# MCU.net
KiCad netlist of a schematic drawn in Altium Designer
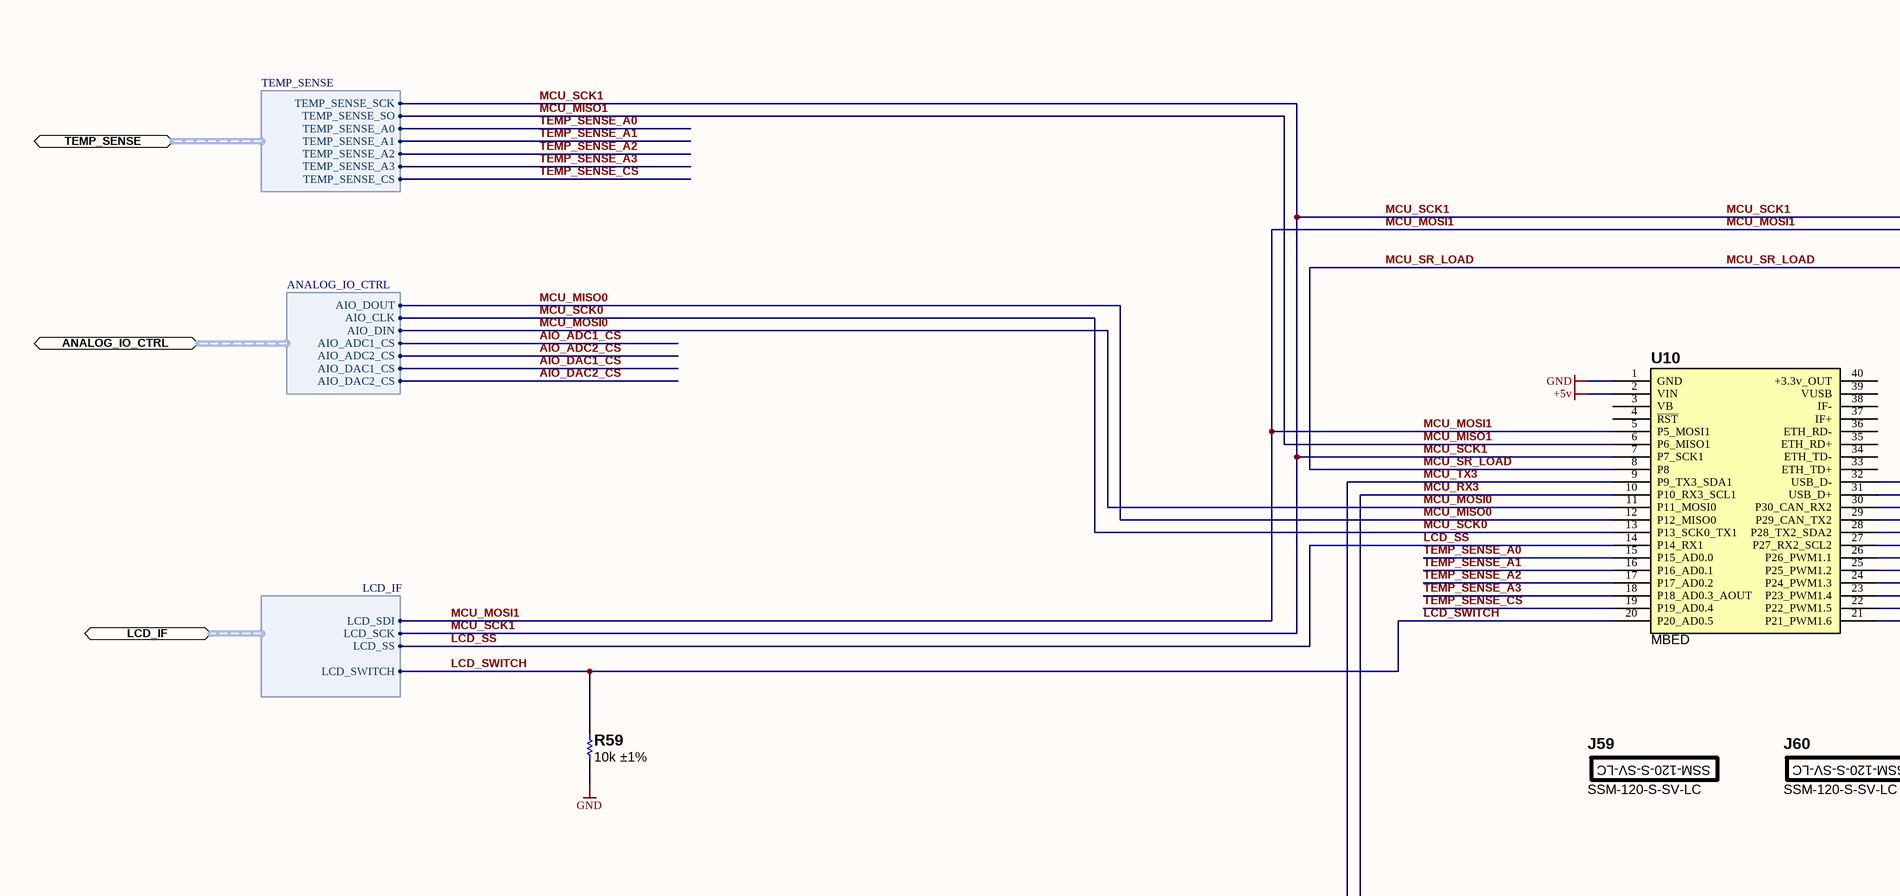
[diagram p0: MCU.SchDoc, top left]
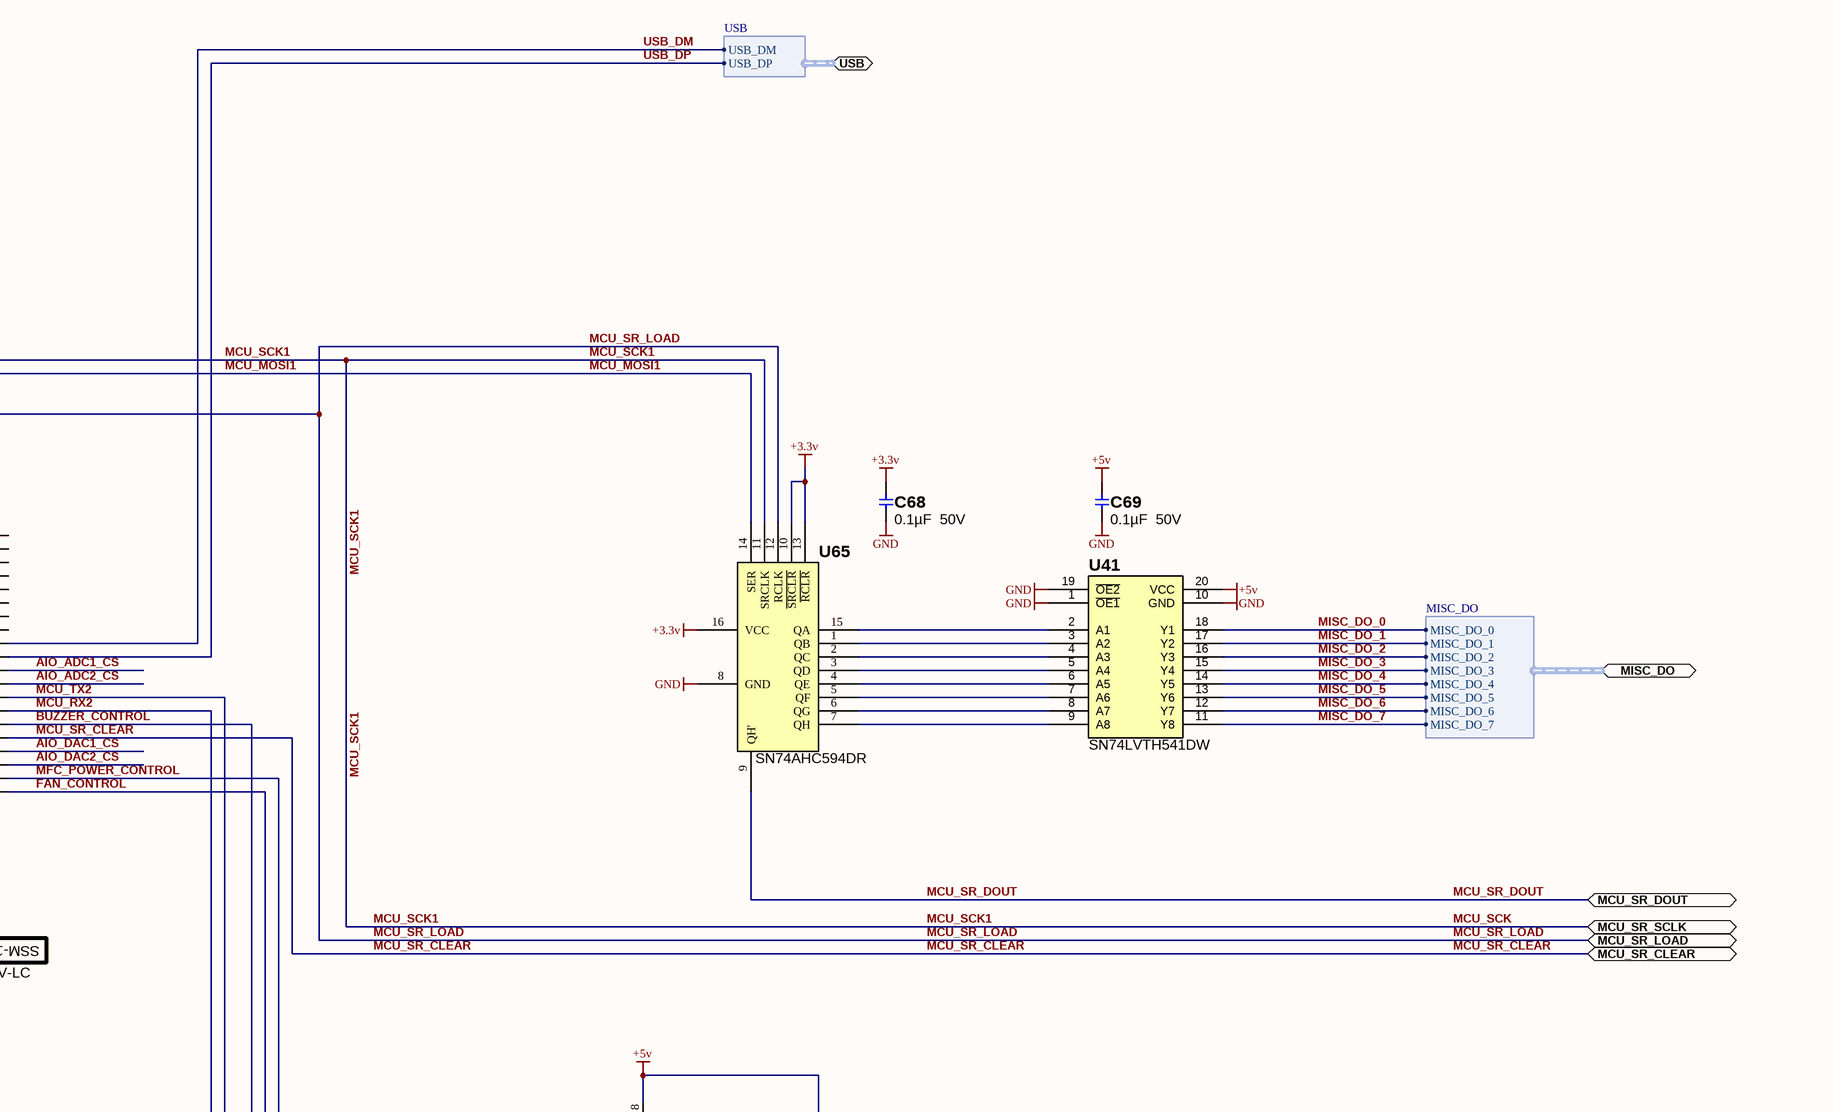
[diagram p1: MCU.SchDoc, top right]
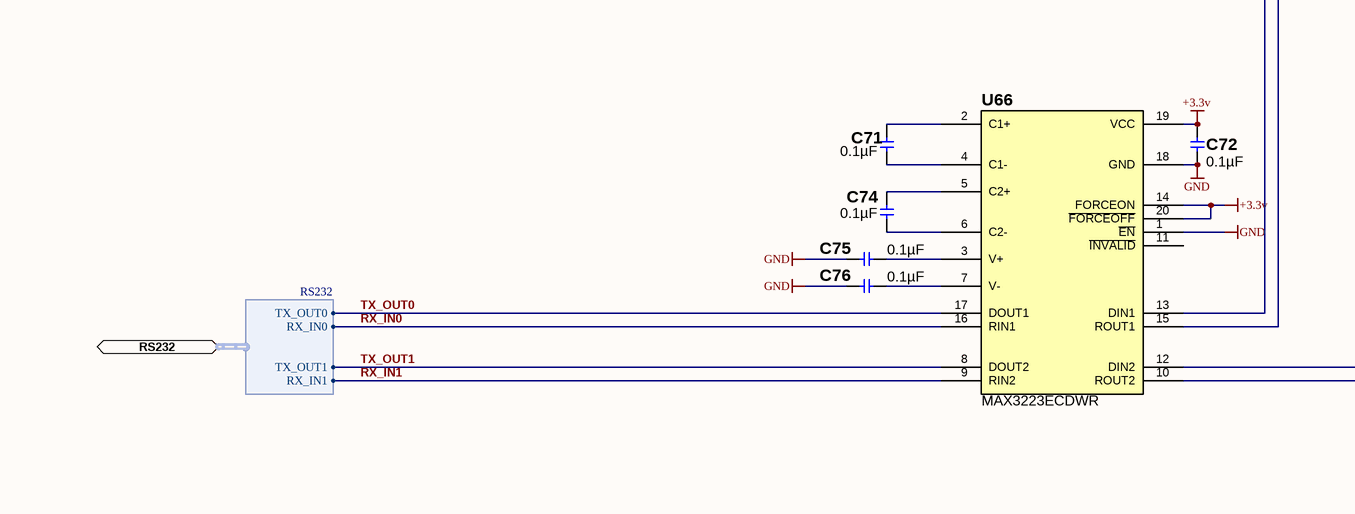
[diagram p2: MCU.SchDoc, bottom left]
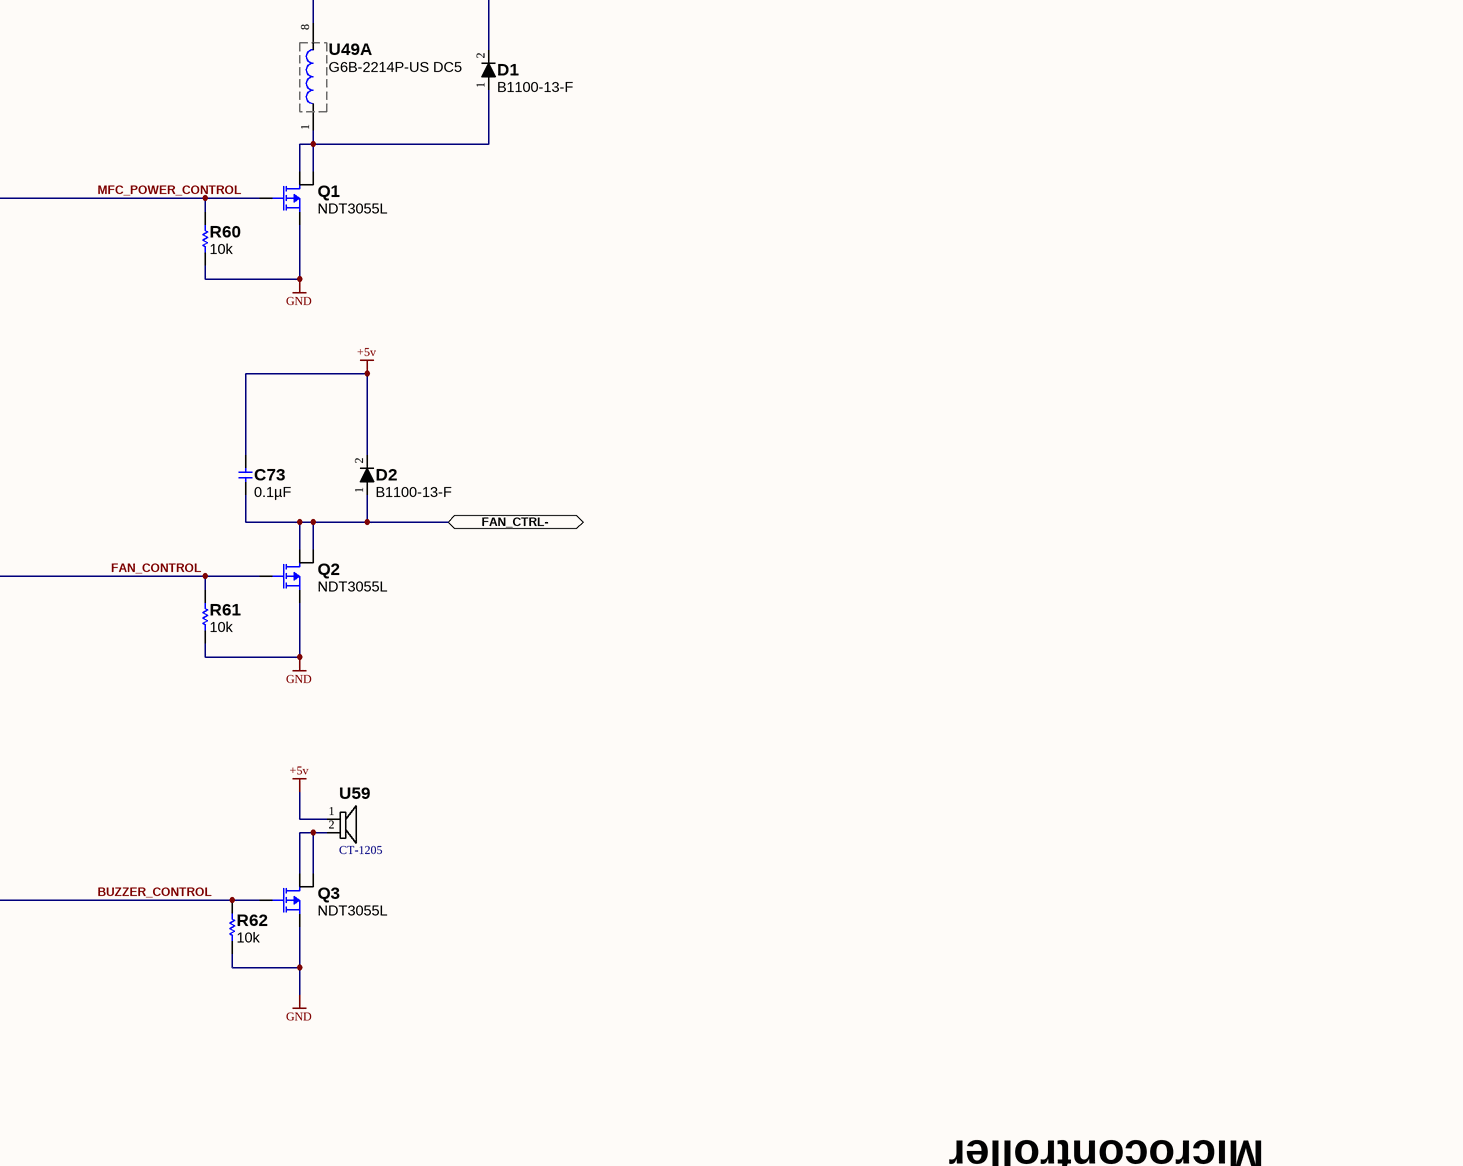
[diagram p3: MCU.SchDoc, bottom right]

(export (version "E")
  (design (tool "Eeschema 10.0.6"))
  (components
    (comp (ref "C68")
      (value "0.1µF  50V")
      (footprint "C0805_LD")
      (description "CAP CER 0.1UF 50V 10% X7R 0805")
      (fields
        (field (name "MANUFACTURER PART NUMBER") "GRM21BR71H104KA01L")
        (field (name "MANUFACTURER") "Murata Electronics North America")
      )
      (libsource (lib "Capacitors") (part "C_2P_NP"))
    )
    (comp (ref "C69")
      (value "0.1µF  50V")
      (footprint "C0805_LD")
      (description "CAP CER 0.1UF 50V 10% X7R 0805")
      (fields
        (field (name "MANUFACTURER PART NUMBER") "GRM21BR71H104KA01L")
        (field (name "MANUFACTURER") "Murata Electronics North America")
      )
      (libsource (lib "Capacitors") (part "C_2P_NP"))
    )
    (comp (ref "C71")
      (value "0.1µF")
      (footprint "C0805_LD")
      (description "CAP CER 0.1UF 50V 10% X7R 0805")
      (fields
        (field (name "MANUFACTURER PART NUMBER") "GRM21BR71H104KA01L")
        (field (name "MANUFACTURER") "Murata Electronics North America")
      )
      (libsource (lib "Capacitors") (part "C_2P_NP"))
    )
    (comp (ref "C72")
      (value "0.1µF")
      (footprint "C0805_LD")
      (description "CAP CER 0.1UF 50V 10% X7R 0805")
      (fields
        (field (name "MANUFACTURER PART NUMBER") "GRM21BR71H104KA01L")
        (field (name "MANUFACTURER") "Murata Electronics North America")
      )
      (libsource (lib "Capacitors") (part "C_2P_NP"))
    )
    (comp (ref "C73")
      (value "0.1µF")
      (footprint "C0805_LD")
      (description "CAP CER 0.1UF 50V 10% X7R 0805")
      (fields
        (field (name "MANUFACTURER PART NUMBER") "GRM21BR71H104KA01L")
        (field (name "MANUFACTURER") "Murata Electronics North America")
      )
      (libsource (lib "Capacitors") (part "C_2P_NP"))
    )
    (comp (ref "C74")
      (value "0.1µF")
      (footprint "C0805_LD")
      (description "CAP CER 0.1UF 50V 10% X7R 0805")
      (fields
        (field (name "MANUFACTURER PART NUMBER") "GRM21BR71H104KA01L")
        (field (name "MANUFACTURER") "Murata Electronics North America")
      )
      (libsource (lib "Capacitors") (part "C_2P_NP"))
    )
    (comp (ref "C75")
      (value "0.1µF")
      (footprint "C0805_LD")
      (description "CAP CER 0.1UF 50V 10% X7R 0805")
      (fields
        (field (name "MANUFACTURER PART NUMBER") "GRM21BR71H104KA01L")
        (field (name "MANUFACTURER") "Murata Electronics North America")
      )
      (libsource (lib "Capacitors") (part "C_2P_NP"))
    )
    (comp (ref "C76")
      (value "0.1µF")
      (footprint "C0805_LD")
      (description "CAP CER 0.1UF 50V 10% X7R 0805")
      (fields
        (field (name "MANUFACTURER PART NUMBER") "GRM21BR71H104KA01L")
        (field (name "MANUFACTURER") "Murata Electronics North America")
      )
      (libsource (lib "Capacitors") (part "C_2P_NP"))
    )
    (comp (ref "D1")
      (value "B1100-13-F")
      (footprint "D_SMA_P")
      (description "DIODE SCHOTTKY 100V 1A SMA")
      (fields (field (name "MANUFACTURER") "Diodes Inc"))
      (libsource (lib "Diodes") (part "DP_1A_2C"))
    )
    (comp (ref "D2")
      (value "B1100-13-F")
      (footprint "D_SMA_P")
      (description "DIODE SCHOTTKY 100V 1A SMA")
      (fields (field (name "MANUFACTURER") "Diodes Inc"))
      (libsource (lib "Diodes") (part "DP_1A_2C"))
    )
    (comp (ref "J59")
      (value "SSM-120-S-SV-LC")
      (description "SAMTEC - SSM-120-S-SV-LC - .025 SOCKET STRIPS")
      (fields (field (name "MANUFACTURER") "SAMTEC"))
      (libsource (lib "151214_2") (part "SSM-120-S-SV-LC (BOM ITEM)"))
    )
    (comp (ref "J60")
      (value "SSM-120-S-SV-LC")
      (description "SAMTEC - SSM-120-S-SV-LC - .025 SOCKET STRIPS")
      (fields (field (name "MANUFACTURER") "SAMTEC"))
      (libsource (lib "151214_2") (part "SSM-120-S-SV-LC (BOM ITEM)"))
    )
    (comp (ref "Q1")
      (value "NDT3055L")
      (footprint "SOT223")
      (description "MOSFET N-CH 60V 4A SOT-223-4")
      (fields (field (name "MANUFACTURER") "Fairchild Semiconductor"))
      (libsource (lib "eTransistor") (part "NDT3055L"))
    )
    (comp (ref "Q2")
      (value "NDT3055L")
      (footprint "SOT223")
      (description "MOSFET N-CH 60V 4A SOT-223-4")
      (fields (field (name "MANUFACTURER") "Fairchild Semiconductor"))
      (libsource (lib "eTransistor") (part "NDT3055L"))
    )
    (comp (ref "Q3")
      (value "NDT3055L")
      (footprint "SOT223")
      (description "MOSFET N-CH 60V 4A SOT-223-4")
      (fields (field (name "MANUFACTURER") "Fairchild Semiconductor"))
      (libsource (lib "eTransistor") (part "NDT3055L"))
    )
    (comp (ref "R59")
      (value "10k ±1%")
      (footprint "R0805_LD")
      (description "RES 10K OHM 1/8W 1% 0805 SMD")
      (fields
        (field (name "MANUFACTURER PART NUMBER") "ERJ-6ENF1002V")
        (field (name "MANUFACTURER") "Panasonic Electronic Components")
      )
      (libsource (lib "Resistors") (part "R_2P"))
    )
    (comp (ref "R60")
      (value "10k")
      (footprint "R0805_LD")
      (description "RES 10K OHM 1/8W 1% 0805 SMD")
      (fields
        (field (name "MANUFACTURER PART NUMBER") "ERJ-6ENF1002V")
        (field (name "MANUFACTURER") "Panasonic Electronic Components")
      )
      (libsource (lib "Resistors") (part "R_2P"))
    )
    (comp (ref "R61")
      (value "10k")
      (footprint "R0805_LD")
      (description "RES 10K OHM 1/8W 1% 0805 SMD")
      (fields
        (field (name "MANUFACTURER PART NUMBER") "ERJ-6ENF1002V")
        (field (name "MANUFACTURER") "Panasonic Electronic Components")
      )
      (libsource (lib "Resistors") (part "R_2P"))
    )
    (comp (ref "R62")
      (value "10k")
      (footprint "R0805_LD")
      (description "RES 10K OHM 1/8W 1% 0805 SMD")
      (fields
        (field (name "MANUFACTURER PART NUMBER") "ERJ-6ENF1002V")
        (field (name "MANUFACTURER") "Panasonic Electronic Components")
      )
      (libsource (lib "Resistors") (part "R_2P"))
    )
    (comp (ref "U10")
      (value "MBED")
      (footprint "MBED_SURFACEMOUNT_SOCKET")
      (description "DEVELOPMENT BOARD LPC1768 MBED")
      (fields
        (field (name "MANUFACTURER") "NXP Semiconductors")
        (field (name "MANUFACTURER PART NUMBER") "OM11043")
      )
      (libsource (lib "eModule") (part "OM11043"))
    )
    (comp (ref "U41")
      (value "SN74LVTH541DW")
      (footprint "SOIC127P1030X265-20L")
      (description "IC BUFF/DVR TRI-ST 8BIT 20SOIC")
      (fields (field (name "MANUFACTURER") "Texas Instruments"))
      (libsource (lib "eIC") (part "SN74LVTH541DW"))
    )
    (comp (ref "U49")
      (value "G6B-2214P-US DC5")
      (footprint "G6B-2214P-US")
      (description "RELAY GENERAL PURPOSE DPST 5A 5V")
      (fields (field (name "MANUFACTURER") "Omron Electronics Inc-EMC Div"))
      (libsource (lib "eElectroMechanical") (part "G6B-2214P-US DC5"))
    )
    (comp (ref "U59")
      (value "CT-1205")
      (footprint "CT-1205")
      (fields (field (name "MANUFACTURER") "CUI Inc") (field (name "SOURCE") "Digikey"))
      (libsource (lib "eAudio") (part "CT-1205"))
    )
    (comp (ref "U65")
      (value "SN74AHC594DR")
      (footprint "SOIC127P600X145-16L")
      (description "IC SHIFT REGISTER 8BIT 16-SOIC")
      (fields (field (name "MANUFACTURER") "Texas Instruments"))
      (libsource (lib "eIC") (part "SN74AHC594DR"))
    )
    (comp (ref "U66")
      (value "MAX3223ECDWR")
      (footprint "SOIC127P1030X265-20L")
      (description "IC RS232 3V5.5V DRVR ESD 20-SOIC")
      (fields (field (name "MANUFACTURER") "Texas Instruments"))
      (libsource (lib "eIC") (part "MAX3223ECDWR"))
    )
  )
  (nets
    (net (code "7") (name "+3.3v") (class "Default")
      (node (ref "C68") (pin "2") (pinfunction "2_2") (pintype "passive"))
      (node (ref "C72") (pin "2") (pinfunction "2_2") (pintype "passive"))
      (node (ref "U65") (pin "10") (pinfunction "~{SRCLR}_10") (pintype "passive"))
      (node (ref "U65") (pin "13") (pinfunction "~{RCLR}_13") (pintype "passive"))
      (node (ref "U65") (pin "16") (pinfunction "VCC_16") (pintype "passive"))
      (node (ref "U66") (pin "14") (pinfunction "FORCEON_14") (pintype "passive"))
      (node (ref "U66") (pin "19") (pinfunction "VCC_19") (pintype "passive"))
      (node (ref "U66") (pin "20") (pinfunction "~{FORCEOFF}_20") (pintype "passive"))
    )
    (net (code "8") (name "+5v") (class "Default")
      (node (ref "C69") (pin "2") (pinfunction "2_2") (pintype "passive"))
      (node (ref "C73") (pin "2") (pinfunction "2_2") (pintype "passive"))
      (node (ref "D1") (pin "2") (pinfunction "K_2") (pintype "passive"))
      (node (ref "D2") (pin "2") (pinfunction "K_2") (pintype "passive"))
      (node (ref "U10") (pin "2") (pinfunction "VIN_2") (pintype "passive"))
      (node (ref "U41") (pin "20") (pinfunction "VCC_20") (pintype "passive"))
      (node (ref "U49") (pin "8") (pinfunction "8_8") (pintype "passive"))
      (node (ref "U59") (pin "1") (pinfunction "+_1") (pintype "passive"))
    )
    (net (code "9") (name "/AIO_ADC1_CS") (class "Default")
      (node (ref "U10") (pin "30") (pinfunction "P30_CAN_RX2_30") (pintype "passive"))
    )
    (net (code "10") (name "/AIO_ADC2_CS") (class "Default")
      (node (ref "U10") (pin "29") (pinfunction "P29_CAN_TX2_29") (pintype "passive"))
    )
    (net (code "11") (name "/AIO_DAC1_CS") (class "Default")
      (node (ref "U10") (pin "24") (pinfunction "P24_PWM1.3_24") (pintype "passive"))
    )
    (net (code "12") (name "/AIO_DAC2_CS") (class "Default")
      (node (ref "U10") (pin "23") (pinfunction "P23_PWM1.4_23") (pintype "passive"))
    )
    (net (code "13") (name "/BUZZER_CONTROL") (class "Default")
      (node (ref "Q3") (pin "1") (pinfunction "G_1") (pintype "passive"))
      (node (ref "R62") (pin "2") (pinfunction "2_2") (pintype "passive"))
      (node (ref "U10") (pin "26") (pinfunction "P26_PWM1.1_26") (pintype "passive"))
    )
    (net (code "14") (name "/FAN_CONTROL") (class "Default")
      (node (ref "Q2") (pin "1") (pinfunction "G_1") (pintype "passive"))
      (node (ref "R61") (pin "2") (pinfunction "2_2") (pintype "passive"))
      (node (ref "U10") (pin "21") (pinfunction "P21_PWM1.6_21") (pintype "passive"))
    )
    (net (code "15") (name "/FAN_CTRL-") (class "Default")
      (node (ref "C73") (pin "1") (pinfunction "1_1") (pintype "passive"))
      (node (ref "D2") (pin "1") (pinfunction "A_1") (pintype "passive"))
      (node (ref "Q2") (pin "2") (pinfunction "D_2") (pintype "passive"))
      (node (ref "Q2") (pin "4") (pinfunction "D_4") (pintype "passive"))
    )
    (net (code "16") (name "/LCD_SS") (class "Default")
      (node (ref "U10") (pin "14") (pinfunction "P14_RX1_14") (pintype "passive"))
    )
    (net (code "17") (name "/LCD_SWITCH") (class "Default")
      (node (ref "R59") (pin "2") (pinfunction "2_2") (pintype "passive"))
      (node (ref "U10") (pin "20") (pinfunction "P20_AD0.5_20") (pintype "passive"))
    )
    (net (code "18") (name "/MCU_MISO0") (class "Default")
      (node (ref "U10") (pin "12") (pinfunction "P12_MISO0_12") (pintype "passive"))
    )
    (net (code "19") (name "/MCU_MISO1") (class "Default")
      (node (ref "U10") (pin "6") (pinfunction "P6_MISO1_6") (pintype "passive"))
    )
    (net (code "20") (name "/MCU_MOSI0") (class "Default")
      (node (ref "U10") (pin "11") (pinfunction "P11_MOSI0_11") (pintype "passive"))
    )
    (net (code "21") (name "/MCU_MOSI1") (class "Default")
      (node (ref "U10") (pin "5") (pinfunction "P5_MOSI1_5") (pintype "passive"))
      (node (ref "U65") (pin "14") (pinfunction "SER_14") (pintype "passive"))
    )
    (net (code "22") (name "/MCU_RX2") (class "Default")
      (node (ref "U10") (pin "27") (pinfunction "P27_RX2_SCL2_27") (pintype "passive"))
      (node (ref "U66") (pin "10") (pinfunction "ROUT2_10") (pintype "passive"))
    )
    (net (code "23") (name "/MCU_RX3") (class "Default")
      (node (ref "U10") (pin "10") (pinfunction "P10_RX3_SCL1_10") (pintype "passive"))
      (node (ref "U66") (pin "15") (pinfunction "ROUT1_15") (pintype "passive"))
    )
    (net (code "24") (name "/MCU_SCK") (class "Default")
      (node (ref "U10") (pin "7") (pinfunction "P7_SCK1_7") (pintype "passive"))
      (node (ref "U65") (pin "11") (pinfunction "SRCLK_11") (pintype "passive"))
    )
    (net (code "25") (name "/MCU_SCK0") (class "Default")
      (node (ref "U10") (pin "13") (pinfunction "P13_SCK0_TX1_13") (pintype "passive"))
    )
    (net (code "26") (name "/MCU_SR_CLEAR") (class "Default")
      (node (ref "U10") (pin "25") (pinfunction "P25_PWM1.2_25") (pintype "passive"))
    )
    (net (code "27") (name "/MCU_SR_DOUT") (class "Default")
      (node (ref "U65") (pin "9") (pinfunction "QH'_9") (pintype "passive"))
    )
    (net (code "28") (name "/MCU_SR_LOAD") (class "Default")
      (node (ref "U10") (pin "8") (pinfunction "P8_8") (pintype "passive"))
      (node (ref "U65") (pin "12") (pinfunction "RCLK_12") (pintype "passive"))
    )
    (net (code "29") (name "/MCU_TX2") (class "Default")
      (node (ref "U10") (pin "28") (pinfunction "P28_TX2_SDA2_28") (pintype "passive"))
      (node (ref "U66") (pin "12") (pinfunction "DIN2_12") (pintype "passive"))
    )
    (net (code "30") (name "/MCU_TX3") (class "Default")
      (node (ref "U10") (pin "9") (pinfunction "P9_TX3_SDA1_9") (pintype "passive"))
      (node (ref "U66") (pin "13") (pinfunction "DIN1_13") (pintype "passive"))
    )
    (net (code "31") (name "/MFC_POWER_CONTROL") (class "Default")
      (node (ref "Q1") (pin "1") (pinfunction "G_1") (pintype "passive"))
      (node (ref "R60") (pin "2") (pinfunction "2_2") (pintype "passive"))
      (node (ref "U10") (pin "22") (pinfunction "P22_PWM1.5_22") (pintype "passive"))
    )
    (net (code "32") (name "/MISC_DO_0") (class "Default")
      (node (ref "U41") (pin "18") (pinfunction "Y1_18") (pintype "passive"))
    )
    (net (code "33") (name "/MISC_DO_1") (class "Default")
      (node (ref "U41") (pin "17") (pinfunction "Y2_17") (pintype "passive"))
    )
    (net (code "34") (name "/MISC_DO_2") (class "Default")
      (node (ref "U41") (pin "16") (pinfunction "Y3_16") (pintype "passive"))
    )
    (net (code "35") (name "/MISC_DO_3") (class "Default")
      (node (ref "U41") (pin "15") (pinfunction "Y4_15") (pintype "passive"))
    )
    (net (code "36") (name "/MISC_DO_4") (class "Default")
      (node (ref "U41") (pin "14") (pinfunction "Y5_14") (pintype "passive"))
    )
    (net (code "37") (name "/MISC_DO_5") (class "Default")
      (node (ref "U41") (pin "13") (pinfunction "Y6_13") (pintype "passive"))
    )
    (net (code "38") (name "/MISC_DO_6") (class "Default")
      (node (ref "U41") (pin "12") (pinfunction "Y7_12") (pintype "passive"))
    )
    (net (code "39") (name "/MISC_DO_7") (class "Default")
      (node (ref "U41") (pin "11") (pinfunction "Y8_11") (pintype "passive"))
    )
    (net (code "40") (name "/RX_IN0") (class "Default")
      (node (ref "U66") (pin "16") (pinfunction "RIN1_16") (pintype "passive"))
    )
    (net (code "41") (name "/RX_IN1") (class "Default")
      (node (ref "U66") (pin "9") (pinfunction "RIN2_9") (pintype "passive"))
    )
    (net (code "42") (name "/TEMP_SENSE_A0") (class "Default")
      (node (ref "U10") (pin "15") (pinfunction "P15_AD0.0_15") (pintype "passive"))
    )
    (net (code "43") (name "/TEMP_SENSE_A1") (class "Default")
      (node (ref "U10") (pin "16") (pinfunction "P16_AD0.1_16") (pintype "passive"))
    )
    (net (code "44") (name "/TEMP_SENSE_A2") (class "Default")
      (node (ref "U10") (pin "17") (pinfunction "P17_AD0.2_17") (pintype "passive"))
    )
    (net (code "45") (name "/TEMP_SENSE_A3") (class "Default")
      (node (ref "U10") (pin "18") (pinfunction "P18_AD0.3_AOUT_18") (pintype "passive"))
    )
    (net (code "46") (name "/TEMP_SENSE_CS") (class "Default")
      (node (ref "U10") (pin "19") (pinfunction "P19_AD0.4_19") (pintype "passive"))
    )
    (net (code "47") (name "/TX_OUT0") (class "Default")
      (node (ref "U66") (pin "17") (pinfunction "DOUT1_17") (pintype "passive"))
    )
    (net (code "48") (name "/TX_OUT1") (class "Default")
      (node (ref "U66") (pin "8") (pinfunction "DOUT2_8") (pintype "passive"))
    )
    (net (code "49") (name "/USB_DM") (class "Default")
      (node (ref "U10") (pin "32") (pinfunction "USB_D-_32") (pintype "passive"))
    )
    (net (code "50") (name "/USB_DP") (class "Default")
      (node (ref "U10") (pin "31") (pinfunction "USB_D+_31") (pintype "passive"))
    )
    (net (code "57") (name "GND") (class "Default")
      (node (ref "C68") (pin "1") (pinfunction "1_1") (pintype "passive"))
      (node (ref "C69") (pin "1") (pinfunction "1_1") (pintype "passive"))
      (node (ref "C72") (pin "1") (pinfunction "1_1") (pintype "passive"))
      (node (ref "C75") (pin "1") (pinfunction "1_1") (pintype "passive"))
      (node (ref "C76") (pin "1") (pinfunction "1_1") (pintype "passive"))
      (node (ref "Q1") (pin "3") (pinfunction "S_3") (pintype "passive"))
      (node (ref "Q2") (pin "3") (pinfunction "S_3") (pintype "passive"))
      (node (ref "Q3") (pin "3") (pinfunction "S_3") (pintype "passive"))
      (node (ref "R59") (pin "1") (pinfunction "1_1") (pintype "passive"))
      (node (ref "R60") (pin "1") (pinfunction "1_1") (pintype "passive"))
      (node (ref "R61") (pin "1") (pinfunction "1_1") (pintype "passive"))
      (node (ref "R62") (pin "1") (pinfunction "1_1") (pintype "passive"))
      (node (ref "U10") (pin "1") (pinfunction "GND_1") (pintype "passive"))
      (node (ref "U41") (pin "1") (pinfunction "~{OE1}_1") (pintype "passive"))
      (node (ref "U41") (pin "10") (pinfunction "GND_10") (pintype "passive"))
      (node (ref "U41") (pin "19") (pinfunction "~{OE2}_19") (pintype "passive"))
      (node (ref "U65") (pin "8") (pinfunction "GND_8") (pintype "passive"))
      (node (ref "U66") (pin "1") (pinfunction "~{EN}_1") (pintype "passive"))
      (node (ref "U66") (pin "18") (pinfunction "GND_18") (pintype "passive"))
    )
    (net (code "58") (name "Net-(D1-A)") (class "Default")
      (node (ref "D1") (pin "1") (pinfunction "A_1") (pintype "passive"))
      (node (ref "Q1") (pin "2") (pinfunction "D_2") (pintype "passive"))
      (node (ref "Q1") (pin "4") (pinfunction "D_4") (pintype "passive"))
      (node (ref "U49") (pin "1") (pinfunction "1_1") (pintype "passive"))
    )
    (net (code "59") (name "Net-(U41-A1)") (class "Default")
      (node (ref "U41") (pin "2") (pinfunction "A1_2") (pintype "passive"))
      (node (ref "U65") (pin "15") (pinfunction "QA_15") (pintype "passive"))
    )
    (net (code "60") (name "Net-(U41-A2)") (class "Default")
      (node (ref "U41") (pin "3") (pinfunction "A2_3") (pintype "passive"))
      (node (ref "U65") (pin "1") (pinfunction "QB_1") (pintype "passive"))
    )
    (net (code "61") (name "Net-(U41-A3)") (class "Default")
      (node (ref "U41") (pin "4") (pinfunction "A3_4") (pintype "passive"))
      (node (ref "U65") (pin "2") (pinfunction "QC_2") (pintype "passive"))
    )
    (net (code "62") (name "Net-(U41-A4)") (class "Default")
      (node (ref "U41") (pin "5") (pinfunction "A4_5") (pintype "passive"))
      (node (ref "U65") (pin "3") (pinfunction "QD_3") (pintype "passive"))
    )
    (net (code "63") (name "Net-(U41-A5)") (class "Default")
      (node (ref "U41") (pin "6") (pinfunction "A5_6") (pintype "passive"))
      (node (ref "U65") (pin "4") (pinfunction "QE_4") (pintype "passive"))
    )
    (net (code "64") (name "Net-(U41-A6)") (class "Default")
      (node (ref "U41") (pin "7") (pinfunction "A6_7") (pintype "passive"))
      (node (ref "U65") (pin "5") (pinfunction "QF_5") (pintype "passive"))
    )
    (net (code "65") (name "Net-(U41-A7)") (class "Default")
      (node (ref "U41") (pin "8") (pinfunction "A7_8") (pintype "passive"))
      (node (ref "U65") (pin "6") (pinfunction "QG_6") (pintype "passive"))
    )
    (net (code "66") (name "Net-(U41-A8)") (class "Default")
      (node (ref "U41") (pin "9") (pinfunction "A8_9") (pintype "passive"))
      (node (ref "U65") (pin "7") (pinfunction "QH_7") (pintype "passive"))
    )
    (net (code "67") (name "Net-(U59--)") (class "Default")
      (node (ref "Q3") (pin "2") (pinfunction "D_2") (pintype "passive"))
      (node (ref "Q3") (pin "4") (pinfunction "D_4") (pintype "passive"))
      (node (ref "U59") (pin "2") (pinfunction "-_2") (pintype "passive"))
    )
    (net (code "68") (name "Net-(U66-C1+)") (class "Default")
      (node (ref "C71") (pin "2") (pinfunction "2_2") (pintype "passive"))
      (node (ref "U66") (pin "2") (pinfunction "C1+_2") (pintype "passive"))
    )
    (net (code "69") (name "Net-(U66-C1-)") (class "Default")
      (node (ref "C71") (pin "1") (pinfunction "1_1") (pintype "passive"))
      (node (ref "U66") (pin "4") (pinfunction "C1-_4") (pintype "passive"))
    )
    (net (code "70") (name "Net-(U66-C2+)") (class "Default")
      (node (ref "C74") (pin "2") (pinfunction "2_2") (pintype "passive"))
      (node (ref "U66") (pin "5") (pinfunction "C2+_5") (pintype "passive"))
    )
    (net (code "71") (name "Net-(U66-C2-)") (class "Default")
      (node (ref "C74") (pin "1") (pinfunction "1_1") (pintype "passive"))
      (node (ref "U66") (pin "6") (pinfunction "C2-_6") (pintype "passive"))
    )
    (net (code "72") (name "Net-(U66-V+)") (class "Default")
      (node (ref "C75") (pin "2") (pinfunction "2_2") (pintype "passive"))
      (node (ref "U66") (pin "3") (pinfunction "V+_3") (pintype "passive"))
    )
    (net (code "73") (name "Net-(U66-V-)") (class "Default")
      (node (ref "C76") (pin "2") (pinfunction "2_2") (pintype "passive"))
      (node (ref "U66") (pin "7") (pinfunction "V-_7") (pintype "passive"))
    )
    (net (code "74") (name "unconnected-(U10-+3.3v_OUT-Pad40)") (class "Default")
      (node (ref "U10") (pin "40") (pinfunction "+3.3v_OUT_40") (pintype "passive"))
    )
    (net (code "75") (name "unconnected-(U10-ETH_RD+-Pad35)") (class "Default")
      (node (ref "U10") (pin "35") (pinfunction "ETH_RD+_35") (pintype "passive"))
    )
    (net (code "76") (name "unconnected-(U10-ETH_RD--Pad36)") (class "Default")
      (node (ref "U10") (pin "36") (pinfunction "ETH_RD-_36") (pintype "passive"))
    )
    (net (code "77") (name "unconnected-(U10-ETH_TD+-Pad33)") (class "Default")
      (node (ref "U10") (pin "33") (pinfunction "ETH_TD+_33") (pintype "passive"))
    )
    (net (code "78") (name "unconnected-(U10-ETH_TD--Pad34)") (class "Default")
      (node (ref "U10") (pin "34") (pinfunction "ETH_TD-_34") (pintype "passive"))
    )
    (net (code "79") (name "unconnected-(U10-IF+-Pad37)") (class "Default")
      (node (ref "U10") (pin "37") (pinfunction "IF+_37") (pintype "passive"))
    )
    (net (code "80") (name "unconnected-(U10-IF--Pad38)") (class "Default")
      (node (ref "U10") (pin "38") (pinfunction "IF-_38") (pintype "passive"))
    )
    (net (code "81") (name "unconnected-(U10-VB-Pad3)") (class "Default")
      (node (ref "U10") (pin "3") (pinfunction "VB_3") (pintype "passive"))
    )
    (net (code "82") (name "unconnected-(U10-VUSB-Pad39)") (class "Default")
      (node (ref "U10") (pin "39") (pinfunction "VUSB_39") (pintype "passive"))
    )
    (net (code "83") (name "unconnected-(U10-~{RST}-Pad4)") (class "Default")
      (node (ref "U10") (pin "4") (pinfunction "~{RST}_4") (pintype "passive"))
    )
    (net (code "84") (name "unconnected-(U66-~{INVALID}-Pad11)") (class "Default")
      (node (ref "U66") (pin "11") (pinfunction "~{INVALID}_11") (pintype "passive"))
    )
  )
)
